# ArbPwrBoost_P4.net
KiCad netlist of a schematic drawn in Altium Designer
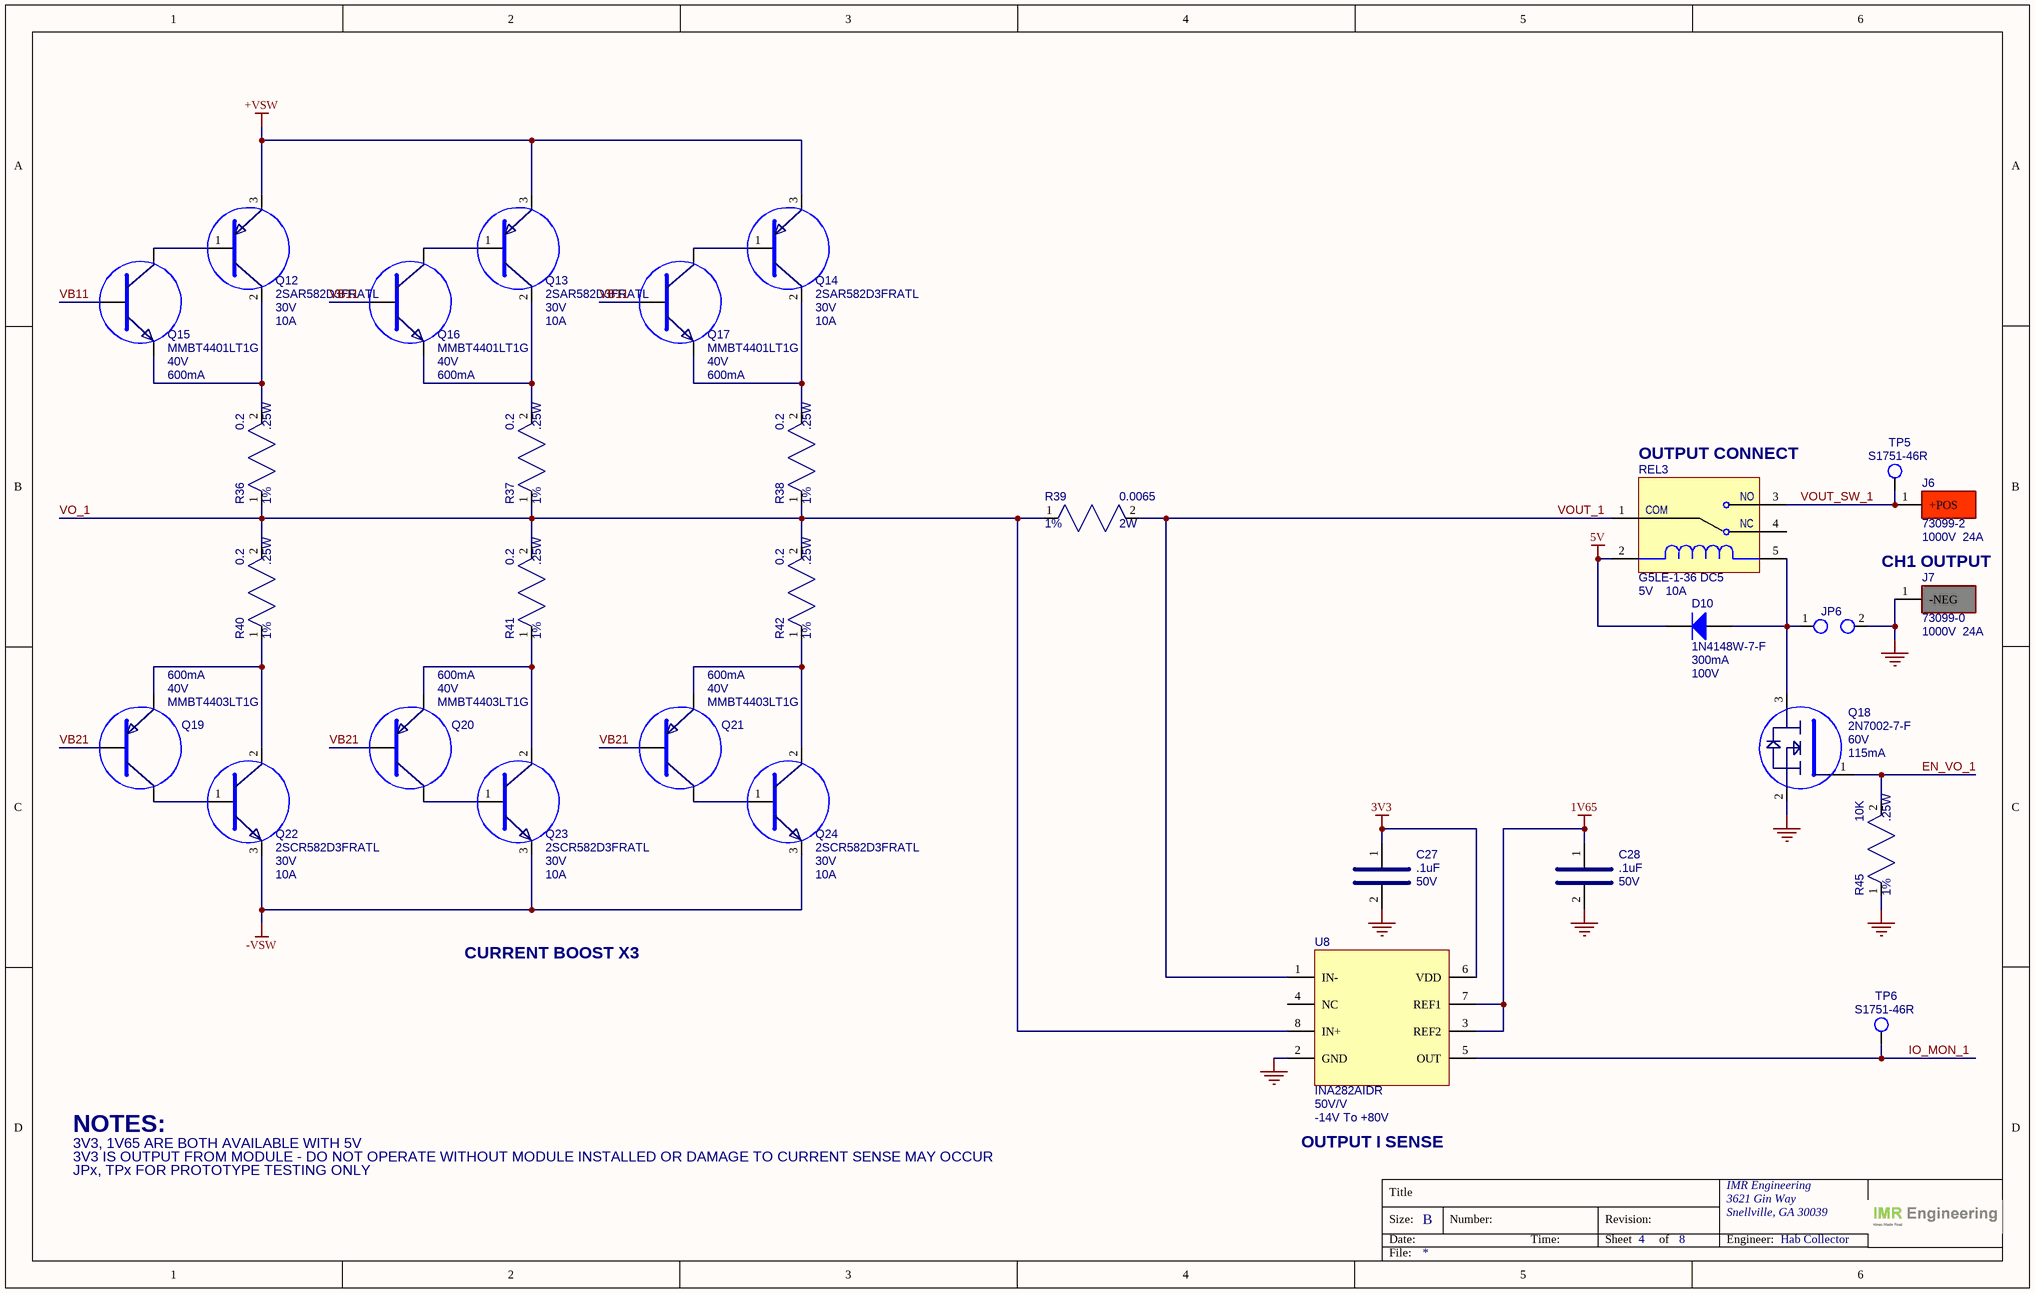
[diagram p0: ArbPwrBoost_P4.SchDoc]

(export (version "E")
  (design (tool "Eeschema 10.0.6"))
  (components
    (comp (ref "C27")
      (value ".1uF")
      (footprint "CAP_0805")
      (description "CAP CER 0.1UF 50V X7R 0805")
      (fields
        (field (name "MFG") "KYOCERA AVX")
        (field (name "VOLTAGE") "50V")
        (field (name "Comment") "KGM21NR71H104KT")
      )
      (libsource (lib "IMR_LIB_SCH_R2") (part "CAP_SMD_0.1UF_50V_0805"))
    )
    (comp (ref "C28")
      (value ".1uF")
      (footprint "CAP_0805")
      (description "CAP CER 0.1UF 50V X7R 0805")
      (fields
        (field (name "MFG") "KYOCERA AVX")
        (field (name "VOLTAGE") "50V")
        (field (name "Comment") "KGM21NR71H104KT")
      )
      (libsource (lib "IMR_LIB_SCH_R2") (part "CAP_SMD_0.1UF_50V_0805"))
    )
    (comp (ref "D10")
      (value "100V")
      (footprint "SOD123")
      (description "RELAY REED SPDT 250MA 5V")
      (fields
        (field (name "MFG") "Diodes Inc")
        (field (name "MFG_PN") "1N4148W-7-F")
        (field (name "CURRENT") "300mA")
        (field (name "Comment") "1N4148W-7-F")
      )
      (libsource (lib "IMR_LIB_SCH_R2") (part "DIODE_1N4148W-7-F"))
    )
    (comp (ref "J6")
      (value "1000V")
      (footprint "Pomona_73099-2")
      (description "CONN 4mm Banana Socket Right Angle PCB RED")
      (fields
        (field (name "MFG") "Pomona")
        (field (name "MFG_PN") "73099-2")
        (field (name "CURRENT") "24A")
        (field (name "Comment") "73099-2")
      )
      (libsource (lib "IMR_LIB_SCH_R2") (part "CONN_PANOMA_73099-2"))
    )
    (comp (ref "J7")
      (value "1000V")
      (footprint "Pomona_73099-0")
      (description "CONN 4mm Banana Socket Right Angle PCB BLK")
      (fields
        (field (name "MFG") "Pomona")
        (field (name "MFG_PN") "73099-0")
        (field (name "CURRENT") "24A")
        (field (name "Comment") "73099-0")
      )
      (libsource (lib "IMR_LIB_SCH_R2") (part "CONN_PANOMA_73099-0"))
    )
    (comp (ref "JP6")
      (value "PREC002SFAN-RC")
      (footprint "HDR_1X2_100MILL")
      (description "CONN HEADER VERT 2POS 2.54MM")
      (fields (field (name "MFG") "Sullins Connector Solutions"))
      (libsource (lib "IMR_LIB_SCH_R2") (part "CONN_JUMPER_2P_100MIL_VERT"))
    )
    (comp (ref "Q12")
      (value "30V")
      (footprint "TO-252")
      (description "TRANS PNP 30V 5.7A TO-252")
      (fields
        (field (name "MFG") "Rohm Semiconductor")
        (field (name "MFG_PN") "2SAR582D3FRATL")
        (field (name "CURRENT") "10A")
        (field (name "Comment") "2SAR582D3FRATL")
      )
      (libsource (lib "IMR_LIB_SCH_R2") (part "BJT_PNP_2SAR582D3FRATL"))
    )
    (comp (ref "Q13")
      (value "30V")
      (footprint "TO-252")
      (description "TRANS PNP 30V 5.7A TO-252")
      (fields
        (field (name "MFG") "Rohm Semiconductor")
        (field (name "MFG_PN") "2SAR582D3FRATL")
        (field (name "CURRENT") "10A")
        (field (name "Comment") "2SAR582D3FRATL")
      )
      (libsource (lib "IMR_LIB_SCH_R2") (part "BJT_PNP_2SAR582D3FRATL"))
    )
    (comp (ref "Q14")
      (value "30V")
      (footprint "TO-252")
      (description "TRANS PNP 30V 5.7A TO-252")
      (fields
        (field (name "MFG") "Rohm Semiconductor")
        (field (name "MFG_PN") "2SAR582D3FRATL")
        (field (name "CURRENT") "10A")
        (field (name "Comment") "2SAR582D3FRATL")
      )
      (libsource (lib "IMR_LIB_SCH_R2") (part "BJT_PNP_2SAR582D3FRATL"))
    )
    (comp (ref "Q15")
      (value "40V")
      (footprint "SOT-23")
      (description "TRANS NPN 40V 0.6A SOT23-3")
      (fields
        (field (name "MFG") "On Semiconductor")
        (field (name "MFG_PN") "MMBT4401LT1G")
        (field (name "CURRENT") "600mA")
        (field (name "Comment") "MMBT4401LT1G")
      )
      (libsource (lib "IMR_LIB_SCH_R2") (part "BJT_NPN_MMBT4401LT1G"))
    )
    (comp (ref "Q16")
      (value "40V")
      (footprint "SOT-23")
      (description "TRANS NPN 40V 0.6A SOT23-3")
      (fields
        (field (name "MFG") "On Semiconductor")
        (field (name "MFG_PN") "MMBT4401LT1G")
        (field (name "CURRENT") "600mA")
        (field (name "Comment") "MMBT4401LT1G")
      )
      (libsource (lib "IMR_LIB_SCH_R2") (part "BJT_NPN_MMBT4401LT1G"))
    )
    (comp (ref "Q17")
      (value "40V")
      (footprint "SOT-23")
      (description "TRANS NPN 40V 0.6A SOT23-3")
      (fields
        (field (name "MFG") "On Semiconductor")
        (field (name "MFG_PN") "MMBT4401LT1G")
        (field (name "CURRENT") "600mA")
        (field (name "Comment") "MMBT4401LT1G")
      )
      (libsource (lib "IMR_LIB_SCH_R2") (part "BJT_NPN_MMBT4401LT1G"))
    )
    (comp (ref "Q18")
      (value "60V")
      (footprint "SOT-23")
      (description "MOSFET N-CH 60V 115MA SOT23-3")
      (fields
        (field (name "MFG") "Diodes Inc")
        (field (name "MFG_PN") "2N7002-7-F")
        (field (name "CURRENT") "115mA")
        (field (name "Comment") "2N7002-7-F")
      )
      (libsource (lib "IMR_LIB_SCH_R2") (part "MOSFET_NCH_2N7002-7-F"))
    )
    (comp (ref "Q19")
      (value "40V")
      (footprint "SOT-23")
      (description "TRANS PNP 40V 0.6A SOT23-3")
      (fields
        (field (name "MFG") "On Semiconductor")
        (field (name "MFG_PN") "MMBT4403LT1G")
        (field (name "CURRENT") "600mA")
        (field (name "Comment") "MMBT4403LT1G")
      )
      (libsource (lib "IMR_LIB_SCH_R2") (part "BJT_PNP_MMBT4403LT1G"))
    )
    (comp (ref "Q20")
      (value "40V")
      (footprint "SOT-23")
      (description "TRANS PNP 40V 0.6A SOT23-3")
      (fields
        (field (name "MFG") "On Semiconductor")
        (field (name "MFG_PN") "MMBT4403LT1G")
        (field (name "CURRENT") "600mA")
        (field (name "Comment") "MMBT4403LT1G")
      )
      (libsource (lib "IMR_LIB_SCH_R2") (part "BJT_PNP_MMBT4403LT1G"))
    )
    (comp (ref "Q21")
      (value "40V")
      (footprint "SOT-23")
      (description "TRANS PNP 40V 0.6A SOT23-3")
      (fields
        (field (name "MFG") "On Semiconductor")
        (field (name "MFG_PN") "MMBT4403LT1G")
        (field (name "CURRENT") "600mA")
        (field (name "Comment") "MMBT4403LT1G")
      )
      (libsource (lib "IMR_LIB_SCH_R2") (part "BJT_PNP_MMBT4403LT1G"))
    )
    (comp (ref "Q22")
      (value "30V")
      (footprint "TO-252")
      (description "TRANS NPN 30V 10A TO-252")
      (fields
        (field (name "MFG") "Rohm Semiconductor")
        (field (name "MFG_PN") "2SCR582D3FRATL")
        (field (name "CURRENT") "10A")
        (field (name "Comment") "2SCR582D3FRATL")
      )
      (libsource (lib "IMR_LIB_SCH_R2") (part "BJT_NPN_2SCR582D3FRATL"))
    )
    (comp (ref "Q23")
      (value "30V")
      (footprint "TO-252")
      (description "TRANS NPN 30V 10A TO-252")
      (fields
        (field (name "MFG") "Rohm Semiconductor")
        (field (name "MFG_PN") "2SCR582D3FRATL")
        (field (name "CURRENT") "10A")
        (field (name "Comment") "2SCR582D3FRATL")
      )
      (libsource (lib "IMR_LIB_SCH_R2") (part "BJT_NPN_2SCR582D3FRATL"))
    )
    (comp (ref "Q24")
      (value "30V")
      (footprint "TO-252")
      (description "TRANS NPN 30V 10A TO-252")
      (fields
        (field (name "MFG") "Rohm Semiconductor")
        (field (name "MFG_PN") "2SCR582D3FRATL")
        (field (name "CURRENT") "10A")
        (field (name "Comment") "2SCR582D3FRATL")
      )
      (libsource (lib "IMR_LIB_SCH_R2") (part "BJT_NPN_2SCR582D3FRATL"))
    )
    (comp (ref "R36")
      (value "0.2")
      (footprint "RES_1206")
      (description "RES SMD 0.2 OHM 1% 1/4W 1206")
      (fields
        (field (name "MFG") "Yageo")
        (field (name "POWER") ".25W")
        (field (name "TOLERANCE") "1%")
        (field (name "Comment") "RL1206FR-070R2L")
      )
      (libsource (lib "IMR_LIB_SCH_R2") (part "RES_SMD_0.2_1206_1/4W_1%"))
    )
    (comp (ref "R37")
      (value "0.2")
      (footprint "RES_1206")
      (description "RES SMD 0.2 OHM 1% 1/4W 1206")
      (fields
        (field (name "MFG") "Yageo")
        (field (name "POWER") ".25W")
        (field (name "TOLERANCE") "1%")
        (field (name "Comment") "RL1206FR-070R2L")
      )
      (libsource (lib "IMR_LIB_SCH_R2") (part "RES_SMD_0.2_1206_1/4W_1%"))
    )
    (comp (ref "R38")
      (value "0.2")
      (footprint "RES_1206")
      (description "RES SMD 0.2 OHM 1% 1/4W 1206")
      (fields
        (field (name "MFG") "Yageo")
        (field (name "POWER") ".25W")
        (field (name "TOLERANCE") "1%")
        (field (name "Comment") "RL1206FR-070R2L")
      )
      (libsource (lib "IMR_LIB_SCH_R2") (part "RES_SMD_0.2_1206_1/4W_1%"))
    )
    (comp (ref "R39")
      (value "0.0065")
      (footprint "RES_2512")
      (description "RES SMD 0.0065 OHM 1% 2W 2512")
      (fields
        (field (name "MFG") "Vishay Dale")
        (field (name "TOLERANCE") "1%")
        (field (name "POWER") "2W")
        (field (name "Comment") "WSL25126L500FEA18")
      )
      (libsource (lib "IMR_LIB_SCH_R2") (part "RES_SMD_0.0065_2512_2W_1%"))
    )
    (comp (ref "R40")
      (value "0.2")
      (footprint "RES_1206")
      (description "RES SMD 0.2 OHM 1% 1/4W 1206")
      (fields
        (field (name "MFG") "Yageo")
        (field (name "POWER") ".25W")
        (field (name "TOLERANCE") "1%")
        (field (name "Comment") "RL1206FR-070R2L")
      )
      (libsource (lib "IMR_LIB_SCH_R2") (part "RES_SMD_0.2_1206_1/4W_1%"))
    )
    (comp (ref "R41")
      (value "0.2")
      (footprint "RES_1206")
      (description "RES SMD 0.2 OHM 1% 1/4W 1206")
      (fields
        (field (name "MFG") "Yageo")
        (field (name "POWER") ".25W")
        (field (name "TOLERANCE") "1%")
        (field (name "Comment") "RL1206FR-070R2L")
      )
      (libsource (lib "IMR_LIB_SCH_R2") (part "RES_SMD_0.2_1206_1/4W_1%"))
    )
    (comp (ref "R42")
      (value "0.2")
      (footprint "RES_1206")
      (description "RES SMD 0.2 OHM 1% 1/4W 1206")
      (fields
        (field (name "MFG") "Yageo")
        (field (name "POWER") ".25W")
        (field (name "TOLERANCE") "1%")
        (field (name "Comment") "RL1206FR-070R2L")
      )
      (libsource (lib "IMR_LIB_SCH_R2") (part "RES_SMD_0.2_1206_1/4W_1%"))
    )
    (comp (ref "R45")
      (value "10K")
      (footprint "RES_0805")
      (description "RES SMD 10K OHM 1% 1/4W 0805")
      (fields
        (field (name "MFG") "Yageo")
        (field (name "POWER") ".25W")
        (field (name "TOLERANCE") "1%")
        (field (name "Comment") "RC0805FR-7W10KL")
      )
      (libsource (lib "IMR_LIB_SCH_R2") (part "RES_SMD_10K_0805_1/4W_1%"))
    )
    (comp (ref "REL3")
      (value "5V")
      (footprint "G5LE")
      (description "RELAY GEN PURPOSE SPDT 10A 5V")
      (fields
        (field (name "MFG") "Omron")
        (field (name "MFG_PN") "G5LE-1-36 DC5")
        (field (name "CURRENT") "10A")
        (field (name "Comment") "G5LE-1-36 DC5")
      )
      (libsource (lib "IMR_LIB_SCH_R2") (part "RELAY_G5LE-1-36 DC5"))
    )
    (comp (ref "TP5")
      (value "S1751-46R")
      (footprint "HARWIN_S1751")
      (description "PCB TEST POINT CONNECT")
      (fields (field (name "MFG") "Harwin Inc") (field (name "MFG_PN") "S1751-46R"))
      (libsource (lib "IMR_LIB_SCH_R2") (part "CONN_TEST_POINT_S1751-46R"))
    )
    (comp (ref "TP6")
      (value "S1751-46R")
      (footprint "HARWIN_S1751")
      (description "PCB TEST POINT CONNECT")
      (fields (field (name "MFG") "Harwin Inc") (field (name "MFG_PN") "S1751-46R"))
      (libsource (lib "IMR_LIB_SCH_R2") (part "CONN_TEST_POINT_S1751-46R"))
    )
    (comp (ref "U8")
      (value "50V/V")
      (footprint "SOIC-8_54")
      (description "IC CURRENT SENSE 0.4% 50V/V SOIC-8")
      (fields
        (field (name "MFG") "Texas Instruments")
        (field (name "COMMON MODE") "-14V To +80V")
        (field (name "MFG_PN") "INA282AIDR")
        (field (name "Comment") "INA282AIDR")
      )
      (libsource (lib "IMR_LIB_SCH_R2") (part "IC_INA282AIDR"))
    )
  )
  (nets
    (net (code "1") (name "+VSW") (class "Default")
      (node (ref "Q12") (pin "3") (pinfunction "E_3") (pintype "passive"))
      (node (ref "Q13") (pin "3") (pinfunction "E_3") (pintype "passive"))
      (node (ref "Q14") (pin "3") (pinfunction "E_3") (pintype "passive"))
    )
    (net (code "2") (name "-VSW") (class "Default")
      (node (ref "Q22") (pin "3") (pinfunction "E_3") (pintype "passive"))
      (node (ref "Q23") (pin "3") (pinfunction "E_3") (pintype "passive"))
      (node (ref "Q24") (pin "3") (pinfunction "E_3") (pintype "passive"))
    )
    (net (code "3") (name "/EN_VO_1") (class "Default")
      (node (ref "Q18") (pin "1") (pinfunction "B_1") (pintype "passive"))
      (node (ref "R45") (pin "2") (pinfunction "2_2") (pintype "passive"))
    )
    (net (code "4") (name "/IO_MON_1") (class "Default")
      (node (ref "TP6") (pin "1") (pintype "passive"))
      (node (ref "U8") (pin "5") (pinfunction "OUT_5") (pintype "passive"))
    )
    (net (code "5") (name "/VB11") (class "Default")
      (node (ref "Q15") (pin "1") (pinfunction "B_1") (pintype "passive"))
      (node (ref "Q16") (pin "1") (pinfunction "B_1") (pintype "passive"))
      (node (ref "Q17") (pin "1") (pinfunction "B_1") (pintype "passive"))
    )
    (net (code "6") (name "/VB21") (class "Default")
      (node (ref "Q19") (pin "1") (pinfunction "B_1") (pintype "passive"))
      (node (ref "Q20") (pin "1") (pinfunction "B_1") (pintype "passive"))
      (node (ref "Q21") (pin "1") (pinfunction "B_1") (pintype "passive"))
    )
    (net (code "7") (name "/VOUT_1") (class "Default")
      (node (ref "R39") (pin "2") (pinfunction "2_2") (pintype "passive"))
      (node (ref "REL3") (pin "1") (pinfunction "COM_1") (pintype "passive"))
      (node (ref "U8") (pin "1") (pinfunction "IN-_1") (pintype "passive"))
    )
    (net (code "8") (name "/VOUT_SW_1") (class "Default")
      (node (ref "J6") (pin "1") (pinfunction "+POS_1") (pintype "passive"))
      (node (ref "REL3") (pin "3") (pinfunction "NO_3") (pintype "passive"))
      (node (ref "TP5") (pin "1") (pintype "passive"))
    )
    (net (code "9") (name "/VO_1") (class "Default")
      (node (ref "R36") (pin "1") (pinfunction "1_1") (pintype "passive"))
      (node (ref "R37") (pin "1") (pinfunction "1_1") (pintype "passive"))
      (node (ref "R38") (pin "1") (pinfunction "1_1") (pintype "passive"))
      (node (ref "R39") (pin "1") (pinfunction "1_1") (pintype "passive"))
      (node (ref "R40") (pin "2") (pinfunction "2_2") (pintype "passive"))
      (node (ref "R41") (pin "2") (pinfunction "2_2") (pintype "passive"))
      (node (ref "R42") (pin "2") (pinfunction "2_2") (pintype "passive"))
      (node (ref "U8") (pin "8") (pinfunction "IN+_8") (pintype "passive"))
    )
    (net (code "10") (name "1V65") (class "Default")
      (node (ref "C28") (pin "1") (pinfunction "1_1") (pintype "passive"))
      (node (ref "U8") (pin "3") (pinfunction "REF2_3") (pintype "passive"))
      (node (ref "U8") (pin "7") (pinfunction "REF1_7") (pintype "passive"))
    )
    (net (code "11") (name "3V3") (class "Default")
      (node (ref "C27") (pin "1") (pinfunction "1_1") (pintype "passive"))
      (node (ref "U8") (pin "6") (pinfunction "VDD_6") (pintype "passive"))
    )
    (net (code "12") (name "5V") (class "Default")
      (node (ref "D10") (pin "2") (pinfunction "K_2") (pintype "passive"))
      (node (ref "REL3") (pin "2") (pintype "passive"))
    )
    (net (code "13") (name "GND") (class "Default")
      (node (ref "C27") (pin "2") (pinfunction "2_2") (pintype "passive"))
      (node (ref "C28") (pin "2") (pinfunction "2_2") (pintype "passive"))
      (node (ref "J7") (pin "1") (pinfunction "-NEG_1") (pintype "passive"))
      (node (ref "JP6") (pin "2") (pintype "passive"))
      (node (ref "Q18") (pin "2") (pinfunction "E_2") (pintype "passive"))
      (node (ref "R45") (pin "1") (pinfunction "1_1") (pintype "passive"))
      (node (ref "U8") (pin "2") (pinfunction "GND_2") (pintype "passive"))
    )
    (net (code "14") (name "Net-(D10-A)") (class "Default")
      (node (ref "D10") (pin "1") (pinfunction "A_1") (pintype "passive"))
      (node (ref "JP6") (pin "1") (pintype "passive"))
      (node (ref "Q18") (pin "3") (pinfunction "C_3") (pintype "passive"))
      (node (ref "REL3") (pin "5") (pintype "passive"))
    )
    (net (code "15") (name "Net-(Q12-B)") (class "Default")
      (node (ref "Q12") (pin "1") (pinfunction "B_1") (pintype "passive"))
      (node (ref "Q15") (pin "3") (pinfunction "C_3") (pintype "passive"))
    )
    (net (code "16") (name "Net-(Q12-C)") (class "Default")
      (node (ref "Q12") (pin "2") (pinfunction "C_2") (pintype "passive"))
      (node (ref "Q15") (pin "2") (pinfunction "E_2") (pintype "passive"))
      (node (ref "R36") (pin "2") (pinfunction "2_2") (pintype "passive"))
    )
    (net (code "17") (name "Net-(Q13-B)") (class "Default")
      (node (ref "Q13") (pin "1") (pinfunction "B_1") (pintype "passive"))
      (node (ref "Q16") (pin "3") (pinfunction "C_3") (pintype "passive"))
    )
    (net (code "18") (name "Net-(Q13-C)") (class "Default")
      (node (ref "Q13") (pin "2") (pinfunction "C_2") (pintype "passive"))
      (node (ref "Q16") (pin "2") (pinfunction "E_2") (pintype "passive"))
      (node (ref "R37") (pin "2") (pinfunction "2_2") (pintype "passive"))
    )
    (net (code "19") (name "Net-(Q14-B)") (class "Default")
      (node (ref "Q14") (pin "1") (pinfunction "B_1") (pintype "passive"))
      (node (ref "Q17") (pin "3") (pinfunction "C_3") (pintype "passive"))
    )
    (net (code "20") (name "Net-(Q14-C)") (class "Default")
      (node (ref "Q14") (pin "2") (pinfunction "C_2") (pintype "passive"))
      (node (ref "Q17") (pin "2") (pinfunction "E_2") (pintype "passive"))
      (node (ref "R38") (pin "2") (pinfunction "2_2") (pintype "passive"))
    )
    (net (code "21") (name "Net-(Q19-C)") (class "Default")
      (node (ref "Q19") (pin "3") (pinfunction "C_3") (pintype "passive"))
      (node (ref "Q22") (pin "1") (pinfunction "B_1") (pintype "passive"))
    )
    (net (code "22") (name "Net-(Q19-E)") (class "Default")
      (node (ref "Q19") (pin "2") (pinfunction "E_2") (pintype "passive"))
      (node (ref "Q22") (pin "2") (pinfunction "C_2") (pintype "passive"))
      (node (ref "R40") (pin "1") (pinfunction "1_1") (pintype "passive"))
    )
    (net (code "23") (name "Net-(Q20-C)") (class "Default")
      (node (ref "Q20") (pin "3") (pinfunction "C_3") (pintype "passive"))
      (node (ref "Q23") (pin "1") (pinfunction "B_1") (pintype "passive"))
    )
    (net (code "24") (name "Net-(Q20-E)") (class "Default")
      (node (ref "Q20") (pin "2") (pinfunction "E_2") (pintype "passive"))
      (node (ref "Q23") (pin "2") (pinfunction "C_2") (pintype "passive"))
      (node (ref "R41") (pin "1") (pinfunction "1_1") (pintype "passive"))
    )
    (net (code "25") (name "Net-(Q21-C)") (class "Default")
      (node (ref "Q21") (pin "3") (pinfunction "C_3") (pintype "passive"))
      (node (ref "Q24") (pin "1") (pinfunction "B_1") (pintype "passive"))
    )
    (net (code "26") (name "Net-(Q21-E)") (class "Default")
      (node (ref "Q21") (pin "2") (pinfunction "E_2") (pintype "passive"))
      (node (ref "Q24") (pin "2") (pinfunction "C_2") (pintype "passive"))
      (node (ref "R42") (pin "1") (pinfunction "1_1") (pintype "passive"))
    )
    (net (code "27") (name "unconnected-(REL3-NC-Pad4)") (class "Default")
      (node (ref "REL3") (pin "4") (pinfunction "NC_4") (pintype "passive"))
    )
    (net (code "28") (name "unconnected-(U8-NC-Pad4)") (class "Default")
      (node (ref "U8") (pin "4") (pinfunction "NC_4") (pintype "passive"))
    )
  )
)
